# amplifier.net
KiCad netlist of a schematic drawn in Altium Designer
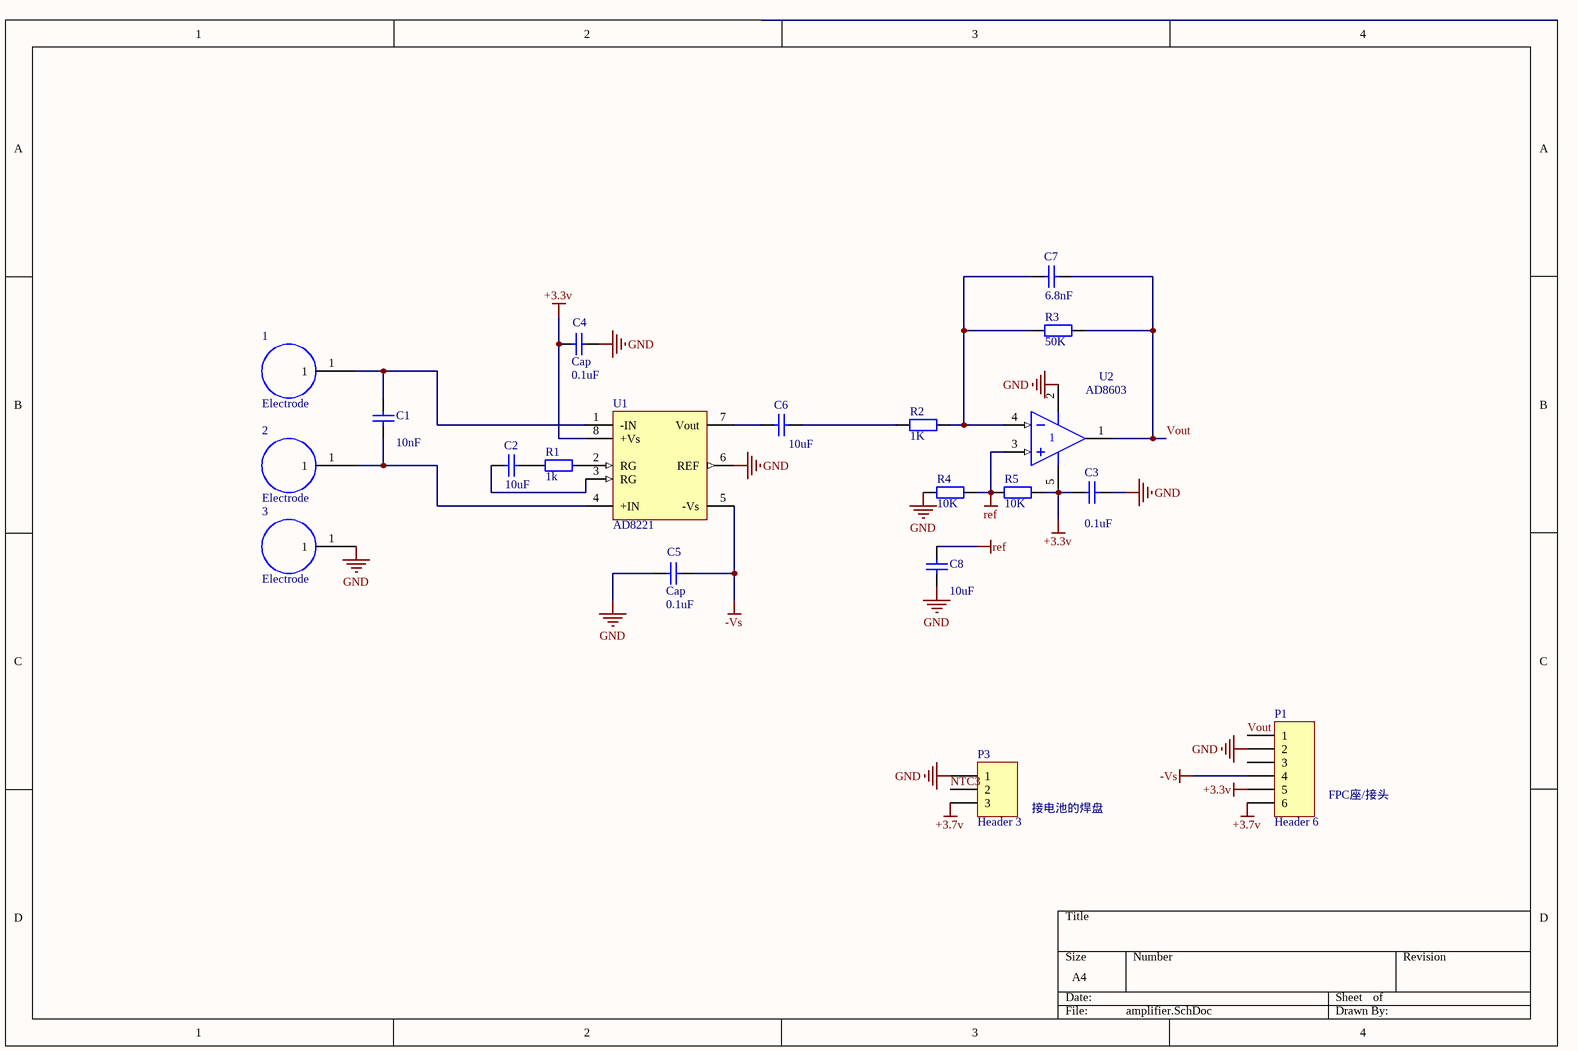
[diagram p0: amplifier.SchDoc]

(export (version "E")
  (design (tool "Eeschema 10.0.6"))
  (components
    (comp (ref "1")
      (value "Electrode")
      (footprint "elec-diff")
      (libsource (lib "My Sch Library") (part "Electrode"))
    )
    (comp (ref "2")
      (value "Electrode")
      (footprint "elec-diff")
      (libsource (lib "My Sch Library") (part "Electrode"))
    )
    (comp (ref "3")
      (value "Electrode")
      (footprint "elec-ref")
      (libsource (lib "My Sch Library") (part "Electrode"))
    )
    (comp (ref "C1")
      (value "10nF")
      (footprint "1608[0603]")
      (description "Capacitor")
      (fields (field (name "PUBLISHER") "Altium Limited"))
      (libsource (lib "Miscellaneous Devices") (part "Cap"))
    )
    (comp (ref "C2")
      (value "10uF")
      (footprint "1608[0603]")
      (description "Capacitor")
      (fields (field (name "PUBLISHER") "Altium Limited"))
      (libsource (lib "Miscellaneous Devices") (part "Cap"))
    )
    (comp (ref "C3")
      (value "0.1uF")
      (footprint "1608[0603]")
      (description "Capacitor")
      (fields (field (name "PUBLISHER") "Altium Limited"))
      (libsource (lib "Miscellaneous Devices") (part "Cap"))
    )
    (comp (ref "C4")
      (value "Cap")
      (footprint "1608[0603]")
      (description "Capacitor")
      (fields (field (name "ALTIUM_VALUE") "0.1uF") (field (name "PUBLISHER") "Altium Limited"))
      (libsource (lib "Miscellaneous Devices") (part "Cap"))
    )
    (comp (ref "C5")
      (value "Cap")
      (footprint "1608[0603]")
      (description "Capacitor")
      (fields (field (name "ALTIUM_VALUE") "0.1uF") (field (name "PUBLISHER") "Altium Limited"))
      (libsource (lib "Miscellaneous Devices") (part "Cap"))
    )
    (comp (ref "C6")
      (value "10uF")
      (footprint "1608[0603]")
      (description "Capacitor")
      (fields (field (name "PUBLISHER") "Altium Limited"))
      (libsource (lib "Miscellaneous Devices") (part "Cap"))
    )
    (comp (ref "C7")
      (value "6.8nF")
      (footprint "1608[0603]")
      (description "Capacitor")
      (fields (field (name "PUBLISHER") "Altium Limited"))
      (libsource (lib "Miscellaneous Devices") (part "Cap"))
    )
    (comp (ref "C8")
      (value "10uF")
      (footprint "1608[0603]")
      (description "Capacitor")
      (fields (field (name "PUBLISHER") "Altium Limited"))
      (libsource (lib "Miscellaneous Devices") (part "Cap"))
    )
    (comp (ref "P1")
      (value "Header 6")
      (footprint "6P_0.5mm(FPC) - duplicate")
      (description "Header, 6-Pin")
      (fields (field (name "PUBLISHER") "Altium Limited"))
      (libsource (lib "Miscellaneous Connectors") (part "Header 6"))
    )
    (comp (ref "P3")
      (value "Header 3")
      (footprint "BAT3")
      (description "Header, 3-Pin")
      (fields (field (name "PUBLISHER") "Altium Limited"))
      (libsource (lib "My Sch Library") (part "Header 3"))
    )
    (comp (ref "R1")
      (value "1k")
      (footprint "1608[0603]")
      (description "Resistor")
      (fields (field (name "PUBLISHER") "Altium Limited"))
      (libsource (lib "") (part "Res2_1"))
    )
    (comp (ref "R2")
      (value "1K")
      (footprint "1608[0603]")
      (description "Resistor")
      (fields (field (name "PUBLISHER") "Altium Limited"))
      (libsource (lib "Miscellaneous Devices") (part "Res2"))
    )
    (comp (ref "R3")
      (value "50K")
      (footprint "1608[0603]")
      (description "Resistor")
      (fields (field (name "PUBLISHER") "Altium Limited"))
      (libsource (lib "Miscellaneous Devices") (part "Res2"))
    )
    (comp (ref "R4")
      (value "10K")
      (footprint "1608[0603]")
      (description "Resistor")
      (fields (field (name "PUBLISHER") "Altium Limited"))
      (libsource (lib "Miscellaneous Devices") (part "Res2"))
    )
    (comp (ref "R5")
      (value "10K")
      (footprint "1608[0603]")
      (description "Resistor")
      (fields (field (name "PUBLISHER") "Altium Limited"))
      (libsource (lib "Miscellaneous Devices") (part "Res2"))
    )
    (comp (ref "U1")
      (value "AD8221")
      (footprint "MSOP-8")
      (description "Precision, Low-Power Instrumentation Amplifiers")
      (fields (field (name "PUBLISHER") "Altium Limited"))
      (libsource (lib "BB Instrumentation Amplifier") (part "INA128UA"))
    )
    (comp (ref "U2")
      (value "AD8603")
      (footprint "SOT23-5AM")
      (libsource (lib "My Sch Library") (part "AD8603"))
    )
  )
  (nets
    (net (code "1") (name "+3.3v") (class "Default")
      (node (ref "C3") (pin "2") (pinfunction "2_2") (pintype "passive"))
      (node (ref "C4") (pin "1") (pinfunction "1_1") (pintype "passive"))
      (node (ref "P1") (pin "5") (pinfunction "5_5") (pintype "passive"))
      (node (ref "R5") (pin "2") (pinfunction "2_2") (pintype "passive"))
      (node (ref "U1") (pin "8") (pinfunction "+Vs_8") (pintype "passive"))
      (node (ref "U2") (pin "5") (pinfunction "V-_5") (pintype "power_in"))
    )
    (net (code "2") (name "+3.7v") (class "Default")
      (node (ref "P1") (pin "6") (pinfunction "6_6") (pintype "passive"))
      (node (ref "P3") (pin "3") (pinfunction "3_3") (pintype "passive"))
    )
    (net (code "3") (name "-Vs") (class "Default")
      (node (ref "C5") (pin "2") (pinfunction "2_2") (pintype "passive"))
      (node (ref "P1") (pin "4") (pinfunction "4_4") (pintype "passive"))
      (node (ref "U1") (pin "5") (pinfunction "-Vs_5") (pintype "passive"))
    )
    (net (code "4") (name "/NTC3") (class "Default")
      (node (ref "P3") (pin "2") (pinfunction "2_2") (pintype "passive"))
    )
    (net (code "5") (name "/Vout") (class "Default")
      (node (ref "C7") (pin "1") (pinfunction "1_1") (pintype "passive"))
      (node (ref "P1") (pin "1") (pinfunction "1_1") (pintype "passive"))
      (node (ref "R3") (pin "2") (pinfunction "2_2") (pintype "passive"))
      (node (ref "U2") (pin "1") (pinfunction "OUT_1") (pintype "passive"))
    )
    (net (code "6") (name "GND") (class "Default")
      (node (ref "3") (pin "1") (pinfunction "1_1") (pintype "passive"))
      (node (ref "C3") (pin "1") (pinfunction "1_1") (pintype "passive"))
      (node (ref "C4") (pin "2") (pinfunction "2_2") (pintype "passive"))
      (node (ref "C5") (pin "1") (pinfunction "1_1") (pintype "passive"))
      (node (ref "C8") (pin "1") (pinfunction "1_1") (pintype "passive"))
      (node (ref "P1") (pin "2") (pinfunction "2_2") (pintype "passive"))
      (node (ref "P3") (pin "1") (pinfunction "1_1") (pintype "passive"))
      (node (ref "R4") (pin "1") (pinfunction "1_1") (pintype "passive"))
      (node (ref "U1") (pin "6") (pinfunction "REF_6") (pintype "output"))
      (node (ref "U2") (pin "2") (pinfunction "V+_2") (pintype "power_in"))
    )
    (net (code "7") (name "Net-(C2-Pad1)") (class "Default")
      (node (ref "C2") (pin "1") (pinfunction "1_1") (pintype "passive"))
      (node (ref "R1") (pin "2") (pinfunction "2_2") (pintype "passive"))
    )
    (net (code "8") (name "Net-(C2-Pad2)") (class "Default")
      (node (ref "C2") (pin "2") (pinfunction "2_2") (pintype "passive"))
      (node (ref "U1") (pin "3") (pinfunction "RG_3") (pintype "input"))
    )
    (net (code "9") (name "Net-(C6-Pad1)") (class "Default")
      (node (ref "C6") (pin "1") (pinfunction "1_1") (pintype "passive"))
      (node (ref "R2") (pin "1") (pinfunction "1_1") (pintype "passive"))
    )
    (net (code "10") (name "Net-(R1-Pad1)") (class "Default")
      (node (ref "R1") (pin "1") (pinfunction "1_1") (pintype "passive"))
      (node (ref "U1") (pin "2") (pinfunction "RG_2") (pintype "input"))
    )
    (net (code "11") (name "Net-(U1-+IN)") (class "Default")
      (node (ref "2") (pin "1") (pinfunction "1_1") (pintype "passive"))
      (node (ref "C1") (pin "1") (pinfunction "1_1") (pintype "passive"))
      (node (ref "U1") (pin "4") (pinfunction "+IN_4") (pintype "power_in"))
    )
    (net (code "12") (name "Net-(U1--IN)") (class "Default")
      (node (ref "1") (pin "1") (pinfunction "1_1") (pintype "passive"))
      (node (ref "C1") (pin "2") (pinfunction "2_2") (pintype "passive"))
      (node (ref "U1") (pin "1") (pinfunction "-IN_1") (pintype "passive"))
    )
    (net (code "13") (name "Net-(U1-Vout)") (class "Default")
      (node (ref "C6") (pin "2") (pinfunction "2_2") (pintype "passive"))
      (node (ref "U1") (pin "7") (pinfunction "Vout_7") (pintype "power_in"))
    )
    (net (code "14") (name "Net-(U2-IN-)") (class "Default")
      (node (ref "C7") (pin "2") (pinfunction "2_2") (pintype "passive"))
      (node (ref "R2") (pin "2") (pinfunction "2_2") (pintype "passive"))
      (node (ref "R3") (pin "1") (pinfunction "1_1") (pintype "passive"))
      (node (ref "U2") (pin "4") (pinfunction "IN-_4") (pintype "input"))
    )
    (net (code "15") (name "ref") (class "Default")
      (node (ref "C8") (pin "2") (pinfunction "2_2") (pintype "passive"))
      (node (ref "R4") (pin "2") (pinfunction "2_2") (pintype "passive"))
      (node (ref "R5") (pin "1") (pinfunction "1_1") (pintype "passive"))
      (node (ref "U2") (pin "3") (pinfunction "IN+_3") (pintype "input"))
    )
    (net (code "16") (name "unconnected-(P1-Pad3)") (class "Default")
      (node (ref "P1") (pin "3") (pinfunction "3_3") (pintype "passive"))
    )
  )
)
